# Eagle.net
KiCad netlist of a schematic drawn in EAGLE
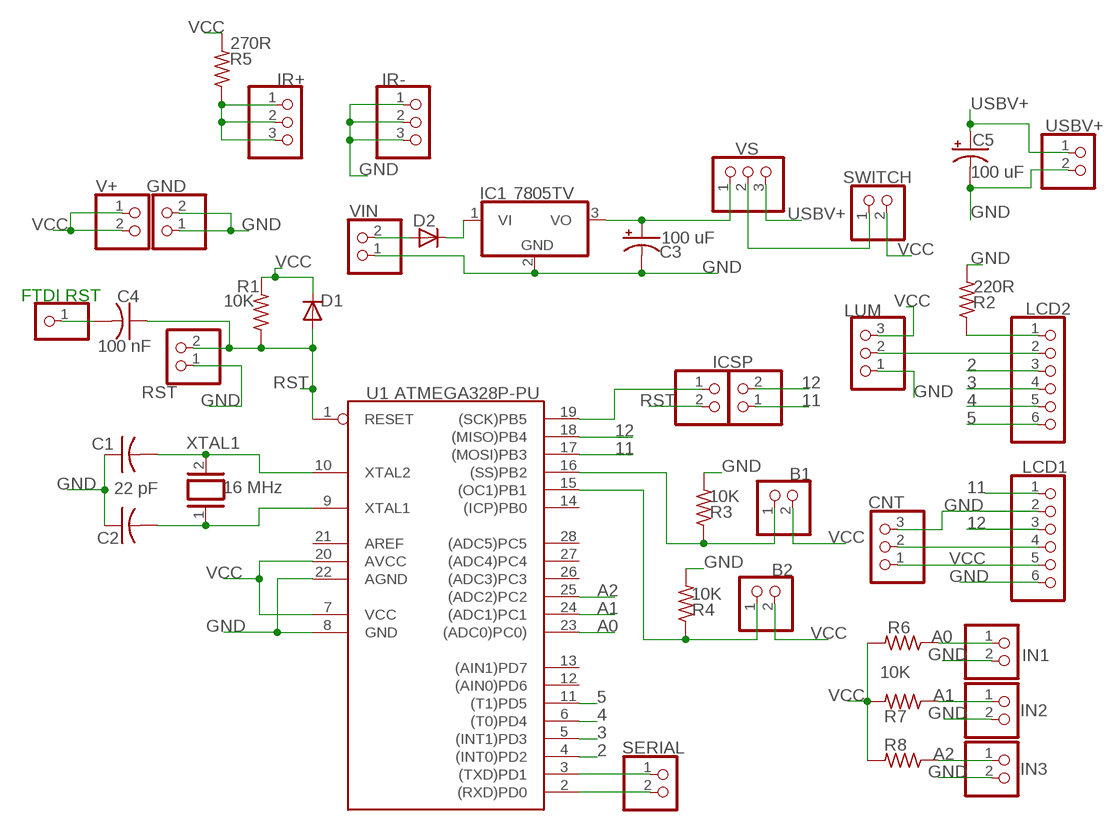
[diagram p0: schematic, sheet 1]

(export (version "E")
  (design (tool "Eeschema 10.0.6"))
  (components
    (comp (ref "B1")
      (value "PINHD-1X2")
      (footprint "eagle-import:1X02")
      (libsource (lib "eagle-import") (part "PINHD-1X2"))
    )
    (comp (ref "B2")
      (value "PINHD-1X2")
      (footprint "eagle-import:1X02")
      (libsource (lib "eagle-import") (part "PINHD-1X2"))
    )
    (comp (ref "C1")
      (value "22 pF")
      (footprint "eagle-import:C025-025X050")
      (libsource (lib "eagle-import") (part "C-US025-025X050"))
    )
    (comp (ref "C2")
      (value "22 pF")
      (footprint "eagle-import:C025-025X050")
      (libsource (lib "eagle-import") (part "C-US025-025X050"))
    )
    (comp (ref "C3")
      (value "100 uF")
      (footprint "eagle-import:E5-6")
      (libsource (lib "eagle-import") (part "rcl_CPOL-USE5-6"))
    )
    (comp (ref "C4")
      (value "100 nF")
      (footprint "eagle-import:C102-043X133")
      (libsource (lib "eagle-import") (part "rcl_C-US102-043X133"))
    )
    (comp (ref "C5")
      (value "100 uF")
      (footprint "eagle-import:B45181A")
      (libsource (lib "eagle-import") (part "CPOL-USB45181A"))
    )
    (comp (ref "CNT")
      (value "PINHD-1X3")
      (footprint "eagle-import:1X03")
      (libsource (lib "eagle-import") (part "PINHD-1X3"))
    )
    (comp (ref "D1")
      (value "1N4148DO35-7")
      (footprint "eagle-import:DO35-7")
      (libsource (lib "eagle-import") (part "1N4148DO35-7"))
    )
    (comp (ref "D2")
      (value "1N4148DO35-7")
      (footprint "eagle-import:DO35-7")
      (libsource (lib "eagle-import") (part "1N4148DO35-7"))
    )
    (comp (ref "FTDI_RST")
      (value "PINHD-1X1")
      (footprint "eagle-import:1X01")
      (libsource (lib "eagle-import") (part "PINHD-1X1"))
    )
    (comp (ref "GND")
      (value "PINHD-1X2")
      (footprint "eagle-import:1X02")
      (libsource (lib "eagle-import") (part "PINHD-1X2"))
    )
    (comp (ref "IC1")
      (value "7805TV")
      (footprint "eagle-import:TO220V")
      (libsource (lib "eagle-import") (part "78TV05"))
    )
    (comp (ref "ICSP")
      (value "PINHD-1X2")
      (footprint "eagle-import:1X02")
      (libsource (lib "eagle-import") (part "PINHD-1X2"))
    )
    (comp (ref "ICSP2")
      (value "PINHD-1X2")
      (footprint "eagle-import:1X02")
      (libsource (lib "eagle-import") (part "PINHD-1X2"))
    )
    (comp (ref "IN1")
      (value "PINHD-1X2")
      (footprint "eagle-import:1X02")
      (libsource (lib "eagle-import") (part "PINHD-1X2"))
    )
    (comp (ref "IN2")
      (value "PINHD-1X2")
      (footprint "eagle-import:1X02")
      (libsource (lib "eagle-import") (part "PINHD-1X2"))
    )
    (comp (ref "IN3")
      (value "PINHD-1X2")
      (footprint "eagle-import:1X02")
      (libsource (lib "eagle-import") (part "PINHD-1X2"))
    )
    (comp (ref "IR+")
      (value "PINHD-1X3")
      (footprint "eagle-import:1X03")
      (libsource (lib "eagle-import") (part "PINHD-1X3"))
    )
    (comp (ref "IR-")
      (value "PINHD-1X3")
      (footprint "eagle-import:1X03")
      (libsource (lib "eagle-import") (part "PINHD-1X3"))
    )
    (comp (ref "LCD1")
      (value "PINHD-1X6")
      (footprint "eagle-import:1X06")
      (libsource (lib "eagle-import") (part "PINHD-1X6"))
    )
    (comp (ref "LCD2")
      (value "PINHD-1X6")
      (footprint "eagle-import:1X06")
      (libsource (lib "eagle-import") (part "PINHD-1X6"))
    )
    (comp (ref "LUM")
      (value "PINHD-1X3")
      (footprint "eagle-import:1X03")
      (libsource (lib "eagle-import") (part "PINHD-1X3"))
    )
    (comp (ref "R1")
      (value "10K")
      (footprint "eagle-import:0204_5")
      (libsource (lib "eagle-import") (part "R-US_0204/5"))
    )
    (comp (ref "R2")
      (value "220R")
      (footprint "eagle-import:0204_5")
      (libsource (lib "eagle-import") (part "R-US_0204/5"))
    )
    (comp (ref "R3")
      (value "10K")
      (footprint "eagle-import:0204_5")
      (libsource (lib "eagle-import") (part "R-US_0204/5"))
    )
    (comp (ref "R4")
      (value "10K")
      (footprint "eagle-import:0204_5")
      (libsource (lib "eagle-import") (part "R-US_0204/5"))
    )
    (comp (ref "R5")
      (value "270R")
      (footprint "eagle-import:0207_10")
      (libsource (lib "eagle-import") (part "R-US_0207/10"))
    )
    (comp (ref "R6")
      (value "10K")
      (footprint "eagle-import:0204_5")
      (libsource (lib "eagle-import") (part "R-US_0204/5"))
    )
    (comp (ref "R7")
      (value "10K")
      (footprint "eagle-import:0204_5")
      (libsource (lib "eagle-import") (part "R-US_0204/5"))
    )
    (comp (ref "R8")
      (value "10K")
      (footprint "eagle-import:0204_5")
      (libsource (lib "eagle-import") (part "R-US_0204/5"))
    )
    (comp (ref "RST")
      (value "PINHD-1X2")
      (footprint "eagle-import:1X02")
      (libsource (lib "eagle-import") (part "PINHD-1X2"))
    )
    (comp (ref "SERIAL")
      (value "PINHD-1X2")
      (footprint "eagle-import:1X02")
      (libsource (lib "eagle-import") (part "PINHD-1X2"))
    )
    (comp (ref "SWITCH")
      (value "PINHD-1X2")
      (footprint "eagle-import:1X02")
      (libsource (lib "eagle-import") (part "PINHD-1X2"))
    )
    (comp (ref "U1")
      (value "ATMEGA328P-PU")
      (footprint "eagle-import:DIL28-3")
      (libsource (lib "eagle-import") (part "ATMEGA328P-PU"))
    )
    (comp (ref "USBV+")
      (value "PINHD-1X2")
      (footprint "eagle-import:1X02")
      (libsource (lib "eagle-import") (part "PINHD-1X2"))
    )
    (comp (ref "V+")
      (value "PINHD-1X2")
      (footprint "eagle-import:1X02")
      (libsource (lib "eagle-import") (part "PINHD-1X2"))
    )
    (comp (ref "VIN")
      (value "PINHD-1X2")
      (footprint "eagle-import:1X02")
      (libsource (lib "eagle-import") (part "PINHD-1X2"))
    )
    (comp (ref "VS")
      (value "PINHD-1X3")
      (footprint "eagle-import:1X03")
      (libsource (lib "eagle-import") (part "PINHD-1X3"))
    )
    (comp (ref "XTAL1")
      (value "16 MHz")
      (footprint "eagle-import:QS")
      (libsource (lib "eagle-import") (part "XTAL/S"))
    )
  )
  (nets
    (net (code "1") (name "/2") (class "Default")
      (node (ref "LCD2") (pin "3") (pinfunction "3_3") (pintype "passive"))
      (node (ref "U1") (pin "4") (pinfunction "(INT0)PD2_4") (pintype "bidirectional"))
    )
    (net (code "2") (name "/3") (class "Default")
      (node (ref "LCD2") (pin "4") (pinfunction "4_4") (pintype "passive"))
      (node (ref "U1") (pin "5") (pinfunction "(INT1)PD3_5") (pintype "bidirectional"))
    )
    (net (code "3") (name "/4") (class "Default")
      (node (ref "LCD2") (pin "5") (pinfunction "5_5") (pintype "passive"))
      (node (ref "U1") (pin "6") (pinfunction "(T0)PD4_6") (pintype "bidirectional"))
    )
    (net (code "4") (name "/5") (class "Default")
      (node (ref "LCD2") (pin "6") (pinfunction "6_6") (pintype "passive"))
      (node (ref "U1") (pin "11") (pinfunction "(T1)PD5_11") (pintype "bidirectional"))
    )
    (net (code "5") (name "/11") (class "Default")
      (node (ref "ICSP2") (pin "1") (pinfunction "1_1") (pintype "passive"))
      (node (ref "LCD1") (pin "1") (pinfunction "1_1") (pintype "passive"))
      (node (ref "U1") (pin "17") (pinfunction "(MOSI)PB3_17") (pintype "bidirectional"))
    )
    (net (code "6") (name "/12") (class "Default")
      (node (ref "ICSP2") (pin "2") (pinfunction "2_2") (pintype "passive"))
      (node (ref "LCD1") (pin "3") (pinfunction "3_3") (pintype "passive"))
      (node (ref "U1") (pin "18") (pinfunction "(MISO)PB4_18") (pintype "bidirectional"))
    )
    (net (code "7") (name "/A0") (class "Default")
      (node (ref "IN1") (pin "1") (pinfunction "1_1") (pintype "passive"))
      (node (ref "R6") (pin "1") (pinfunction "1_1") (pintype "passive"))
      (node (ref "U1") (pin "23") (pinfunction "(ADC0)PC0)_23") (pintype "bidirectional"))
    )
    (net (code "8") (name "/A1") (class "Default")
      (node (ref "IN2") (pin "1") (pinfunction "1_1") (pintype "passive"))
      (node (ref "R7") (pin "1") (pinfunction "1_1") (pintype "passive"))
      (node (ref "U1") (pin "24") (pinfunction "(ADC1)PC1_24") (pintype "bidirectional"))
    )
    (net (code "9") (name "/A2") (class "Default")
      (node (ref "IN3") (pin "1") (pinfunction "1_1") (pintype "passive"))
      (node (ref "R8") (pin "1") (pinfunction "1_1") (pintype "passive"))
      (node (ref "U1") (pin "25") (pinfunction "(ADC2)PC2_25") (pintype "bidirectional"))
    )
    (net (code "10") (name "/GND") (class "Default")
      (node (ref "C1") (pin "1") (pinfunction "1_1") (pintype "passive"))
      (node (ref "C2") (pin "1") (pinfunction "1_1") (pintype "passive"))
      (node (ref "C3") (pin "-") (pinfunction "-_-") (pintype "passive"))
      (node (ref "C5") (pin "-") (pinfunction "-_-") (pintype "passive"))
      (node (ref "CNT") (pin "3") (pinfunction "3_3") (pintype "passive"))
      (node (ref "GND") (pin "1") (pinfunction "1_1") (pintype "passive"))
      (node (ref "GND") (pin "2") (pinfunction "2_2") (pintype "passive"))
      (node (ref "IC1") (pin "2") (pinfunction "GND_2") (pintype "passive"))
      (node (ref "IN1") (pin "2") (pinfunction "2_2") (pintype "passive"))
      (node (ref "IN2") (pin "2") (pinfunction "2_2") (pintype "passive"))
      (node (ref "IN3") (pin "2") (pinfunction "2_2") (pintype "passive"))
      (node (ref "IR-") (pin "1") (pinfunction "1_1") (pintype "passive"))
      (node (ref "IR-") (pin "2") (pinfunction "2_2") (pintype "passive"))
      (node (ref "IR-") (pin "3") (pinfunction "3_3") (pintype "passive"))
      (node (ref "LCD1") (pin "2") (pinfunction "2_2") (pintype "passive"))
      (node (ref "LCD1") (pin "6") (pinfunction "6_6") (pintype "passive"))
      (node (ref "LUM") (pin "1") (pinfunction "1_1") (pintype "passive"))
      (node (ref "R2") (pin "2") (pinfunction "2_2") (pintype "passive"))
      (node (ref "R3") (pin "2") (pinfunction "2_2") (pintype "passive"))
      (node (ref "R4") (pin "2") (pinfunction "2_2") (pintype "passive"))
      (node (ref "RST") (pin "1") (pinfunction "1_1") (pintype "passive"))
      (node (ref "U1") (pin "22") (pinfunction "AGND_22") (pintype "power_in"))
      (node (ref "U1") (pin "8") (pinfunction "GND_8") (pintype "power_in"))
      (node (ref "USBV+") (pin "2") (pinfunction "2_2") (pintype "passive"))
      (node (ref "VIN") (pin "1") (pinfunction "1_1") (pintype "passive"))
    )
    (net (code "11") (name "/RST") (class "Default")
      (node (ref "C4") (pin "1") (pinfunction "1_1") (pintype "passive"))
      (node (ref "D1") (pin "A") (pinfunction "A_A") (pintype "passive"))
      (node (ref "ICSP") (pin "2") (pinfunction "2_2") (pintype "passive"))
      (node (ref "R1") (pin "1") (pinfunction "1_1") (pintype "passive"))
      (node (ref "RST") (pin "2") (pinfunction "2_2") (pintype "passive"))
      (node (ref "U1") (pin "1") (pinfunction "RESET_1") (pintype "input"))
    )
    (net (code "12") (name "/USBV+") (class "Default")
      (node (ref "C5") (pin "+") (pinfunction "+_+") (pintype "passive"))
      (node (ref "USBV+") (pin "1") (pinfunction "1_1") (pintype "passive"))
      (node (ref "VS") (pin "3") (pinfunction "3_3") (pintype "passive"))
    )
    (net (code "13") (name "/VCC") (class "Default")
      (node (ref "B1") (pin "2") (pinfunction "2_2") (pintype "passive"))
      (node (ref "B2") (pin "2") (pinfunction "2_2") (pintype "passive"))
      (node (ref "CNT") (pin "1") (pinfunction "1_1") (pintype "passive"))
      (node (ref "D1") (pin "C") (pinfunction "C_C") (pintype "passive"))
      (node (ref "LCD1") (pin "5") (pinfunction "5_5") (pintype "passive"))
      (node (ref "LUM") (pin "3") (pinfunction "3_3") (pintype "passive"))
      (node (ref "R1") (pin "2") (pinfunction "2_2") (pintype "passive"))
      (node (ref "R5") (pin "2") (pinfunction "2_2") (pintype "passive"))
      (node (ref "R6") (pin "2") (pinfunction "2_2") (pintype "passive"))
      (node (ref "R7") (pin "2") (pinfunction "2_2") (pintype "passive"))
      (node (ref "R8") (pin "2") (pinfunction "2_2") (pintype "passive"))
      (node (ref "SWITCH") (pin "2") (pinfunction "2_2") (pintype "passive"))
      (node (ref "U1") (pin "20") (pinfunction "AVCC_20") (pintype "power_in"))
      (node (ref "U1") (pin "7") (pinfunction "VCC_7") (pintype "power_in"))
      (node (ref "V+") (pin "1") (pinfunction "1_1") (pintype "passive"))
      (node (ref "V+") (pin "2") (pinfunction "2_2") (pintype "passive"))
    )
    (net (code "14") (name "Net-(C4-Pad2)") (class "Default")
      (node (ref "C4") (pin "2") (pinfunction "2_2") (pintype "passive"))
      (node (ref "FTDI_RST") (pin "1") (pinfunction "1_1") (pintype "passive"))
    )
    (net (code "15") (name "Net-(CNT-Pad2)") (class "Default")
      (node (ref "CNT") (pin "2") (pinfunction "2_2") (pintype "passive"))
      (node (ref "LCD1") (pin "4") (pinfunction "4_4") (pintype "passive"))
    )
    (net (code "16") (name "Net-(D2-PadA)") (class "Default")
      (node (ref "D2") (pin "A") (pinfunction "A_A") (pintype "passive"))
      (node (ref "VIN") (pin "2") (pinfunction "2_2") (pintype "passive"))
    )
    (net (code "17") (name "Net-(IC1-VI)") (class "Default")
      (node (ref "D2") (pin "C") (pinfunction "C_C") (pintype "passive"))
      (node (ref "IC1") (pin "1") (pinfunction "VI_1") (pintype "input"))
    )
    (net (code "18") (name "Net-(IC1-VO)") (class "Default")
      (node (ref "C3") (pin "+") (pinfunction "+_+") (pintype "passive"))
      (node (ref "IC1") (pin "3") (pinfunction "VO_3") (pintype "passive"))
      (node (ref "VS") (pin "1") (pinfunction "1_1") (pintype "passive"))
    )
    (net (code "19") (name "Net-(IR+-Pad1)") (class "Default")
      (node (ref "IR+") (pin "1") (pinfunction "1_1") (pintype "passive"))
      (node (ref "IR+") (pin "2") (pinfunction "2_2") (pintype "passive"))
      (node (ref "IR+") (pin "3") (pinfunction "3_3") (pintype "passive"))
      (node (ref "R5") (pin "1") (pinfunction "1_1") (pintype "passive"))
    )
    (net (code "20") (name "Net-(LCD2-Pad1)") (class "Default")
      (node (ref "LCD2") (pin "1") (pinfunction "1_1") (pintype "passive"))
      (node (ref "R2") (pin "1") (pinfunction "1_1") (pintype "passive"))
    )
    (net (code "21") (name "Net-(LCD2-Pad2)") (class "Default")
      (node (ref "LCD2") (pin "2") (pinfunction "2_2") (pintype "passive"))
      (node (ref "LUM") (pin "2") (pinfunction "2_2") (pintype "passive"))
    )
    (net (code "22") (name "Net-(SWITCH-Pad1)") (class "Default")
      (node (ref "SWITCH") (pin "1") (pinfunction "1_1") (pintype "passive"))
      (node (ref "VS") (pin "2") (pinfunction "2_2") (pintype "passive"))
    )
    (net (code "23") (name "Net-(U1-(OC1)PB1)") (class "Default")
      (node (ref "B2") (pin "1") (pinfunction "1_1") (pintype "passive"))
      (node (ref "R4") (pin "1") (pinfunction "1_1") (pintype "passive"))
      (node (ref "U1") (pin "15") (pinfunction "(OC1)PB1_15") (pintype "bidirectional"))
    )
    (net (code "24") (name "Net-(U1-(RXD)PD0)") (class "Default")
      (node (ref "SERIAL") (pin "2") (pinfunction "2_2") (pintype "passive"))
      (node (ref "U1") (pin "2") (pinfunction "(RXD)PD0_2") (pintype "bidirectional"))
    )
    (net (code "25") (name "Net-(U1-(SCK)PB5)") (class "Default")
      (node (ref "ICSP") (pin "1") (pinfunction "1_1") (pintype "passive"))
      (node (ref "U1") (pin "19") (pinfunction "(SCK)PB5_19") (pintype "bidirectional"))
    )
    (net (code "26") (name "Net-(U1-(SS)PB2)") (class "Default")
      (node (ref "B1") (pin "1") (pinfunction "1_1") (pintype "passive"))
      (node (ref "R3") (pin "1") (pinfunction "1_1") (pintype "passive"))
      (node (ref "U1") (pin "16") (pinfunction "(SS)PB2_16") (pintype "bidirectional"))
    )
    (net (code "27") (name "Net-(U1-(TXD)PD1)") (class "Default")
      (node (ref "SERIAL") (pin "1") (pinfunction "1_1") (pintype "passive"))
      (node (ref "U1") (pin "3") (pinfunction "(TXD)PD1_3") (pintype "bidirectional"))
    )
    (net (code "28") (name "Net-(U1-XTAL1)") (class "Default")
      (node (ref "C2") (pin "2") (pinfunction "2_2") (pintype "passive"))
      (node (ref "U1") (pin "9") (pinfunction "XTAL1_9") (pintype "bidirectional"))
      (node (ref "XTAL1") (pin "1") (pinfunction "1_1") (pintype "passive"))
    )
    (net (code "29") (name "Net-(U1-XTAL2)") (class "Default")
      (node (ref "C1") (pin "2") (pinfunction "2_2") (pintype "passive"))
      (node (ref "U1") (pin "10") (pinfunction "XTAL2_10") (pintype "bidirectional"))
      (node (ref "XTAL1") (pin "2") (pinfunction "2_2") (pintype "passive"))
    )
    (net (code "30") (name "unconnected-(U1-(ADC3)PC3-Pad26)") (class "Default")
      (node (ref "U1") (pin "26") (pinfunction "(ADC3)PC3_26") (pintype "bidirectional"))
    )
    (net (code "31") (name "unconnected-(U1-(ADC4)PC4-Pad27)") (class "Default")
      (node (ref "U1") (pin "27") (pinfunction "(ADC4)PC4_27") (pintype "bidirectional"))
    )
    (net (code "32") (name "unconnected-(U1-(ADC5)PC5-Pad28)") (class "Default")
      (node (ref "U1") (pin "28") (pinfunction "(ADC5)PC5_28") (pintype "bidirectional"))
    )
    (net (code "33") (name "unconnected-(U1-(AIN0)PD6-Pad12)") (class "Default")
      (node (ref "U1") (pin "12") (pinfunction "(AIN0)PD6_12") (pintype "bidirectional"))
    )
    (net (code "34") (name "unconnected-(U1-(AIN1)PD7-Pad13)") (class "Default")
      (node (ref "U1") (pin "13") (pinfunction "(AIN1)PD7_13") (pintype "bidirectional"))
    )
    (net (code "35") (name "unconnected-(U1-(ICP)PB0-Pad14)") (class "Default")
      (node (ref "U1") (pin "14") (pinfunction "(ICP)PB0_14") (pintype "bidirectional"))
    )
    (net (code "36") (name "unconnected-(U1-AREF-Pad21)") (class "Default")
      (node (ref "U1") (pin "21") (pinfunction "AREF_21") (pintype "passive"))
    )
  )
)
